# design.net
KiCad netlist of a schematic drawn in Altium Designer
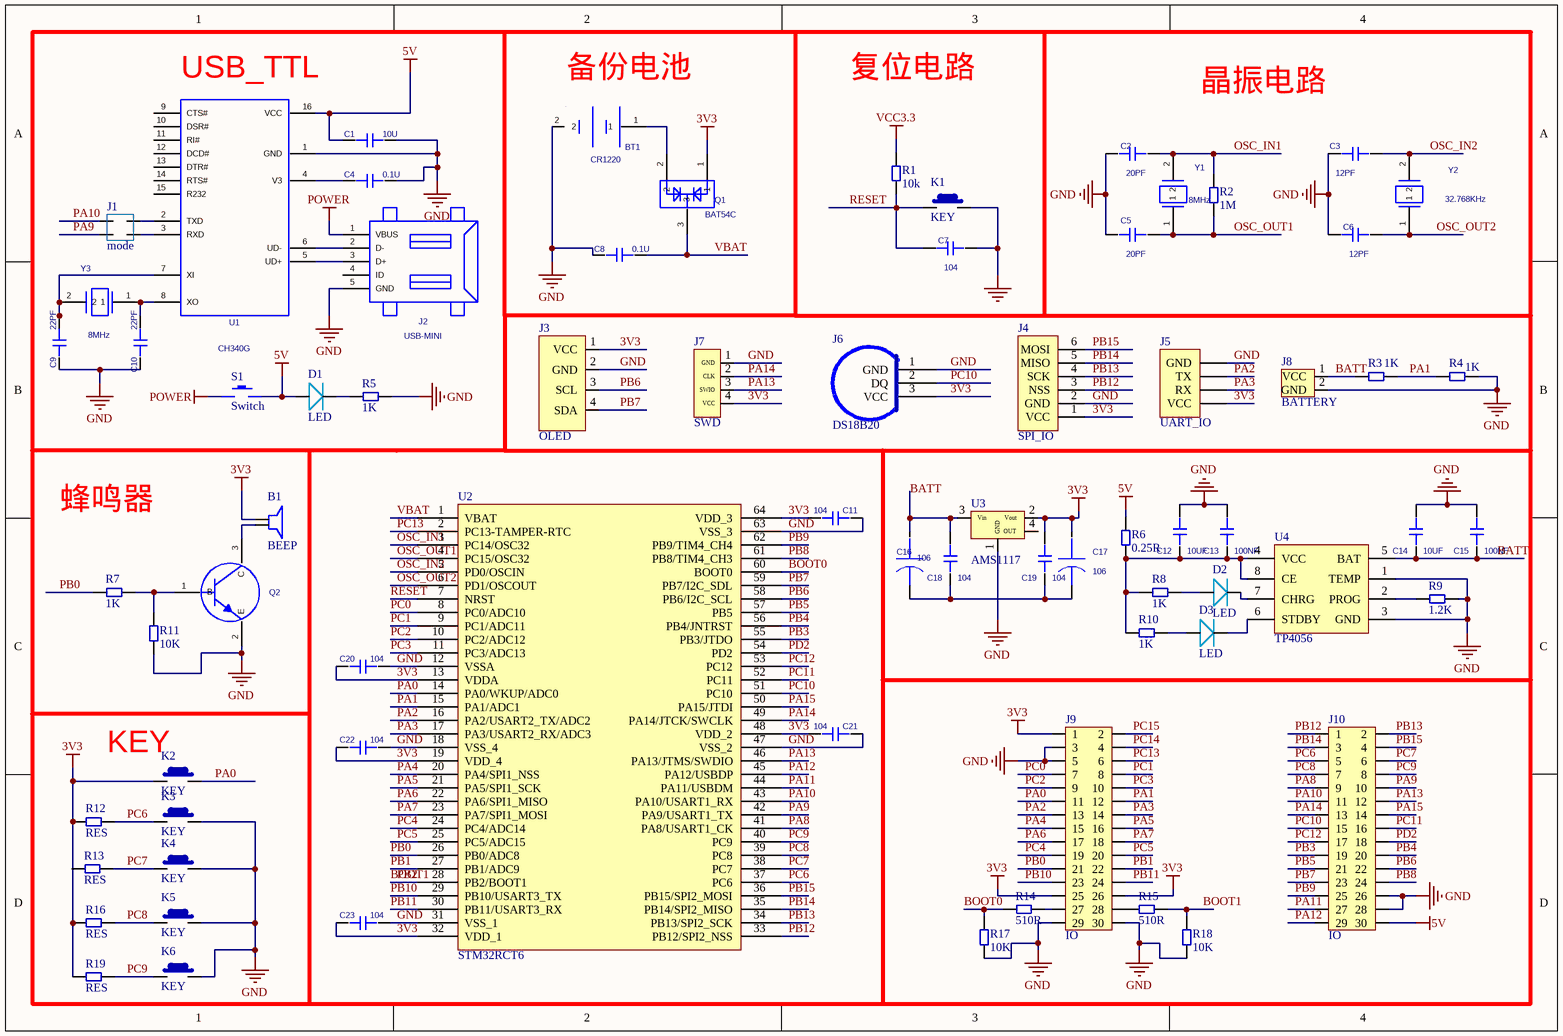
[diagram p0: 创意时钟.SchDoc]

(export (version "E")
  (design (tool "Eeschema 10.0.6"))
  (components
    (comp (ref "B1") (value "BEEP") (footprint "BEEP-9.5X5.5") (libsource (lib "AG") (part "BEEP")))
    (comp (ref "BT1") (value "CR1220") (footprint "BATERY") (libsource (lib "MINI-V3") (part "CR1220")))
    (comp (ref "C1")
      (value "10U")
      (footprint "RES_0603_FIRE")
      (description "0603")
      (fields (field (name "TOLERANCE") "+-5%") (field (name "Comment") "CAP_10P_0603_FIRE"))
      (libsource (lib "MINI-V3") (part "CAP_10P_0603_FIRE"))
    )
    (comp (ref "C2")
      (value "20PF")
      (footprint "CAP_0603_FIRE")
      (fields (field (name "Comment") "CAP_20P_0603_FIRE"))
      (libsource (lib "MINI-V3") (part "CAP_20P_0603_FIRE"))
    )
    (comp (ref "C3")
      (value "12PF")
      (footprint "CAP_0603_FIRE")
      (fields (field (name "Comment") "CAP_20P_0603_FIRE"))
      (libsource (lib "MINI-V3") (part "CAP_20P_0603_FIRE"))
    )
    (comp (ref "C4")
      (value "0.1U")
      (footprint "RES_0603_FIRE")
      (description "0603")
      (fields (field (name "TOLERANCE") "+-5%") (field (name "Comment") "CAP_10P_0603_FIRE"))
      (libsource (lib "MINI-V3") (part "CAP_10P_0603_FIRE"))
    )
    (comp (ref "C5")
      (value "20PF")
      (footprint "CAP_0603_FIRE")
      (fields (field (name "Comment") "CAP_20P_0603_FIRE"))
      (libsource (lib "MINI-V3") (part "CAP_20P_0603_FIRE"))
    )
    (comp (ref "C6")
      (value "12PF")
      (footprint "CAP_0603_FIRE")
      (fields (field (name "Comment") "CAP_20P_0603_FIRE"))
      (libsource (lib "MINI-V3") (part "CAP_20P_0603_FIRE"))
    )
    (comp (ref "C7")
      (value "104")
      (footprint "CAP_0603_FIRE")
      (fields (field (name "Comment") "CAP_20P_0603_FIRE"))
      (libsource (lib "MINI-V3") (part "CAP_20P_0603_FIRE"))
    )
    (comp (ref "C8")
      (value "0.1U")
      (footprint "RES_0603_FIRE")
      (description "0603")
      (fields (field (name "TOLERANCE") "+-5%") (field (name "Comment") "CAP_10P_0603_FIRE"))
      (libsource (lib "MINI-V3") (part "CAP_10P_0603_FIRE"))
    )
    (comp (ref "C9")
      (value "22PF")
      (footprint "CAP_0603_FIRE")
      (fields (field (name "Comment") "CAP_20P_0603_FIRE"))
      (libsource (lib "MINI-V3") (part "CAP_20P_0603_FIRE"))
    )
    (comp (ref "C10")
      (value "22PF")
      (footprint "CAP_0603_FIRE")
      (fields (field (name "Comment") "CAP_20P_0603_FIRE"))
      (libsource (lib "MINI-V3") (part "CAP_20P_0603_FIRE"))
    )
    (comp (ref "C11")
      (value "104")
      (footprint "CAP_0603_FIRE")
      (fields (field (name "Comment") "CAP_20P_0603_FIRE"))
      (libsource (lib "MINI-V3") (part "CAP_20P_0603_FIRE"))
    )
    (comp (ref "C12")
      (value "10UF")
      (footprint "RES_0603_FIRE")
      (description "0603")
      (fields (field (name "TOLERANCE") "+-5%") (field (name "Comment") "CAP_10P_0603_FIRE"))
      (libsource (lib "MINI-V3") (part "CAP_10P_0603_FIRE"))
    )
    (comp (ref "C13")
      (value "100NF")
      (footprint "RES_0603_FIRE")
      (description "0603")
      (fields (field (name "TOLERANCE") "+-5%") (field (name "Comment") "CAP_10P_0603_FIRE"))
      (libsource (lib "MINI-V3") (part "CAP_10P_0603_FIRE"))
    )
    (comp (ref "C14")
      (value "10UF")
      (footprint "RES_0603_FIRE")
      (description "0603")
      (fields (field (name "TOLERANCE") "+-5%") (field (name "Comment") "CAP_10P_0603_FIRE"))
      (libsource (lib "MINI-V3") (part "CAP_10P_0603_FIRE"))
    )
    (comp (ref "C15")
      (value "100NF")
      (footprint "RES_0603_FIRE")
      (description "0603")
      (fields (field (name "TOLERANCE") "+-5%") (field (name "Comment") "CAP_10P_0603_FIRE"))
      (libsource (lib "MINI-V3") (part "CAP_10P_0603_FIRE"))
    )
    (comp (ref "C16")
      (value "106")
      (footprint "CAP+_47UF_FIRE")
      (fields (field (name "Comment") "CAP+_47UF_FIRE"))
      (libsource (lib "MINI-V3") (part "CAP+_47UF_FIRE"))
    )
    (comp (ref "C17")
      (value "106")
      (footprint "CAP+_47UF_FIRE")
      (fields (field (name "Comment") "CAP+_47UF_FIRE"))
      (libsource (lib "MINI-V3") (part "CAP+_47UF_FIRE"))
    )
    (comp (ref "C18")
      (value "104")
      (footprint "RES_0603_FIRE")
      (description "0603")
      (fields (field (name "TOLERANCE") "+-5%") (field (name "Comment") "CAP_10P_0603_FIRE"))
      (libsource (lib "MINI-V3") (part "CAP_10P_0603_FIRE"))
    )
    (comp (ref "C19")
      (value "104")
      (footprint "RES_0603_FIRE")
      (description "0603")
      (fields (field (name "TOLERANCE") "+-5%") (field (name "Comment") "CAP_10P_0603_FIRE"))
      (libsource (lib "MINI-V3") (part "CAP_10P_0603_FIRE"))
    )
    (comp (ref "C20")
      (value "104")
      (footprint "CAP_0603_FIRE")
      (fields (field (name "Comment") "CAP_20P_0603_FIRE"))
      (libsource (lib "MINI-V3") (part "CAP_20P_0603_FIRE"))
    )
    (comp (ref "C21")
      (value "104")
      (footprint "CAP_0603_FIRE")
      (fields (field (name "Comment") "CAP_20P_0603_FIRE"))
      (libsource (lib "MINI-V3") (part "CAP_20P_0603_FIRE"))
    )
    (comp (ref "C22")
      (value "104")
      (footprint "CAP_0603_FIRE")
      (fields (field (name "Comment") "CAP_20P_0603_FIRE"))
      (libsource (lib "MINI-V3") (part "CAP_20P_0603_FIRE"))
    )
    (comp (ref "C23")
      (value "104")
      (footprint "CAP_0603_FIRE")
      (fields (field (name "Comment") "CAP_20P_0603_FIRE"))
      (libsource (lib "MINI-V3") (part "CAP_20P_0603_FIRE"))
    )
    (comp (ref "D1") (value "LED") (footprint "0603_R_JX") (libsource (lib "Schlib1") (part "LED")))
    (comp (ref "D2") (value "LED") (footprint "0603_R_JX") (libsource (lib "Schlib1") (part "LED")))
    (comp (ref "D3") (value "LED") (footprint "0603_R_JX") (libsource (lib "Schlib1") (part "LED")))
    (comp (ref "J1") (value "mode") (footprint "mode") (libsource (lib "Schlib1") (part "mode")))
    (comp (ref "J2")
      (value "USB-MINI")
      (footprint "USB_MINI_B_FE_JX")
      (libsource (lib "MINI-V3") (part "USB-MINI"))
    )
    (comp (ref "J3") (value "OLED") (footprint "OLED") (libsource (lib "aaa") (part "OLED")))
    (comp (ref "J4") (value "SPI_IO") (footprint "SPI_IO") (libsource (lib "Schlib1") (part "SPI_IO")))
    (comp (ref "J5") (value "UART_IO") (footprint "USART_IO") (libsource (lib "Schlib1") (part "UART_IO")))
    (comp (ref "J6") (value "DS18B20") (footprint "DS18B20") (libsource (lib "Schlib1") (part "DS18B20")))
    (comp (ref "J7") (value "SWD") (footprint "SWD") (libsource (lib "aaa") (part "SWD")))
    (comp (ref "J8")
      (value "BATTERY")
      (footprint "XH_2501R_2P_LOCKED_JX")
      (libsource (lib "Schlib1") (part "BATTER"))
    )
    (comp (ref "J9") (value "IO") (footprint "IO") (libsource (lib "Schlib1") (part "IO")))
    (comp (ref "J10") (value "IO") (footprint "IO") (libsource (lib "Schlib1") (part "IO")))
    (comp (ref "K1") (value "KEY") (footprint "KEY") (libsource (lib "Schlib1") (part "KEY")))
    (comp (ref "K2") (value "KEY") (footprint "KEY") (libsource (lib "Schlib1") (part "KEY")))
    (comp (ref "K3") (value "KEY") (footprint "KEY") (libsource (lib "Schlib1") (part "KEY")))
    (comp (ref "K4") (value "KEY") (footprint "KEY") (libsource (lib "Schlib1") (part "KEY")))
    (comp (ref "K5") (value "KEY") (footprint "KEY") (libsource (lib "Schlib1") (part "KEY")))
    (comp (ref "K6") (value "KEY") (footprint "KEY") (libsource (lib "Schlib1") (part "KEY")))
    (comp (ref "Q1") (value "BAT54C") (footprint "SOT-23") (libsource (lib "MINI-V3") (part "BAT54C")))
    (comp (ref "Q2")
      (value "8050")
      (footprint "SOT-23")
      (description "NPN")
      (libsource (lib "MINI-V3") (part "8050"))
    )
    (comp (ref "R1") (value "10k") (footprint "0805") (libsource (lib "Schlib1") (part "RES")))
    (comp (ref "R2") (value "1M") (footprint "0805") (libsource (lib "Schlib1") (part "RES")))
    (comp (ref "R3") (value "1K") (footprint "0805") (libsource (lib "Schlib1") (part "RES")))
    (comp (ref "R4") (value "1K") (footprint "0805") (libsource (lib "Schlib1") (part "RES")))
    (comp (ref "R5") (value "1K") (footprint "0805") (libsource (lib "Schlib1") (part "RES")))
    (comp (ref "R6") (value "0.25R") (footprint "0805") (libsource (lib "Schlib1") (part "RES")))
    (comp (ref "R7") (value "1K") (footprint "0805") (libsource (lib "Schlib1") (part "RES")))
    (comp (ref "R8") (value "1K") (footprint "0805") (libsource (lib "Schlib1") (part "RES")))
    (comp (ref "R9") (value "1.2K") (footprint "0805") (libsource (lib "Schlib1") (part "RES")))
    (comp (ref "R10") (value "1K") (footprint "0805") (libsource (lib "Schlib1") (part "RES")))
    (comp (ref "R11") (value "10K") (footprint "0805") (libsource (lib "Schlib1") (part "RES")))
    (comp (ref "R12") (value "RES") (footprint "0805") (libsource (lib "Schlib1") (part "RES")))
    (comp (ref "R13") (value "RES") (footprint "0805") (libsource (lib "Schlib1") (part "RES")))
    (comp (ref "R14") (value "510R") (footprint "0805") (libsource (lib "Schlib1") (part "RES")))
    (comp (ref "R15") (value "510R") (footprint "0805") (libsource (lib "Schlib1") (part "RES")))
    (comp (ref "R16") (value "RES") (footprint "0805") (libsource (lib "Schlib1") (part "RES")))
    (comp (ref "R17") (value "10K") (footprint "0805") (libsource (lib "Schlib1") (part "RES")))
    (comp (ref "R18") (value "10K") (footprint "0805") (libsource (lib "Schlib1") (part "RES")))
    (comp (ref "R19") (value "RES") (footprint "0805") (libsource (lib "Schlib1") (part "RES")))
    (comp (ref "S1") (value "Switch") (footprint "SWITCH") (libsource (lib "aaa") (part "Switch")))
    (comp (ref "U1") (value "CH340G") (footprint "SOP16") (libsource (lib "MINI-V3") (part "CH340G")))
    (comp (ref "U2") (value "STM32RCT6") (footprint "LQFP64") (libsource (lib "Schlib1") (part "STM32RCT6")))
    (comp (ref "U3") (value "AMS1117") (footprint "AMS-1117-3.3") (libsource (lib "aaa") (part "AMS1117")))
    (comp (ref "U4")
      (value "TP4056")
      (footprint "SOP8_150MIL_JX")
      (libsource (lib "Schlib1") (part "TP4056"))
    )
    (comp (ref "Y1")
      (value "8MHz")
      (footprint "XTAL_socket")
      (description "CRYSTAL")
      (fields (field (name "Comment") "XTAL_8M_FIRE"))
      (libsource (lib "MINI-V3") (part "XTAL_8M_FIRE"))
    )
    (comp (ref "Y2")
      (value "32.768KHz")
      (footprint "CRYS-3X8")
      (description "CRYSTAL")
      (fields (field (name "Comment") "XTAL_32.768KHZ_FIRE"))
      (libsource (lib "MINI-V3") (part "XTAL_32.768KHZ_FIRE"))
    )
    (comp (ref "Y3")
      (value "8MHz")
      (footprint "XTAL_socket")
      (description "CRYSTAL")
      (fields (field (name "Comment") "XTAL_8M_FIRE"))
      (libsource (lib "MINI-V3") (part "XTAL_8M_FIRE"))
    )
  )
  (nets
    (net (code "1") (name "/BATT") (class "Default")
      (node (ref "C14") (pin "1") (pinfunction "1_1") (pintype "passive"))
      (node (ref "C15") (pin "1") (pinfunction "1_1") (pintype "passive"))
      (node (ref "C16") (pin "1") (pinfunction "1_1") (pintype "passive"))
      (node (ref "C18") (pin "2") (pinfunction "2_2") (pintype "passive"))
      (node (ref "J8") (pin "1") (pinfunction "VCC_1") (pintype "passive"))
      (node (ref "R3") (pin "1") (pintype "passive"))
      (node (ref "U3") (pin "3") (pinfunction "Vin_3") (pintype "passive"))
      (node (ref "U4") (pin "5") (pinfunction "BAT_5") (pintype "passive"))
    )
    (net (code "2") (name "/BOOT0") (class "Default")
      (node (ref "R14") (pin "1") (pintype "passive"))
      (node (ref "R17") (pin "2") (pintype "passive"))
      (node (ref "U2") (pin "60") (pinfunction "BOOT0_60") (pintype "passive"))
    )
    (net (code "3") (name "/BOOT1") (class "Default")
      (node (ref "R15") (pin "2") (pintype "passive"))
      (node (ref "R18") (pin "2") (pintype "passive"))
      (node (ref "U2") (pin "28") (pinfunction "PB2/BOOT1_28") (pintype "passive"))
    )
    (net (code "4") (name "/OSC_IN1") (class "Default")
      (node (ref "C2") (pin "2") (pinfunction "2_2") (pintype "passive"))
      (node (ref "R2") (pin "2") (pintype "passive"))
      (node (ref "U2") (pin "3") (pinfunction "PC14/OSC32_3") (pintype "passive"))
      (node (ref "Y1") (pin "2") (pinfunction "2_2") (pintype "passive"))
    )
    (net (code "5") (name "/OSC_IN2") (class "Default")
      (node (ref "C3") (pin "2") (pinfunction "2_2") (pintype "passive"))
      (node (ref "U2") (pin "5") (pinfunction "PD0/OSCIN_5") (pintype "passive"))
      (node (ref "Y2") (pin "2") (pinfunction "2_2") (pintype "passive"))
    )
    (net (code "6") (name "/OSC_OUT1") (class "Default")
      (node (ref "C5") (pin "2") (pinfunction "2_2") (pintype "passive"))
      (node (ref "R2") (pin "1") (pintype "passive"))
      (node (ref "U2") (pin "4") (pinfunction "PC15/OSC32_4") (pintype "passive"))
      (node (ref "Y1") (pin "1") (pinfunction "1_1") (pintype "passive"))
    )
    (net (code "7") (name "/OSC_OUT2") (class "Default")
      (node (ref "C6") (pin "2") (pinfunction "2_2") (pintype "passive"))
      (node (ref "U2") (pin "6") (pinfunction "PD1/OSCOUT_6") (pintype "passive"))
      (node (ref "Y2") (pin "1") (pinfunction "1_1") (pintype "passive"))
    )
    (net (code "8") (name "/PA0") (class "Default")
      (node (ref "J9") (pin "11") (pinfunction "11_11") (pintype "passive"))
      (node (ref "K2") (pin "2") (pintype "passive"))
      (node (ref "U2") (pin "14") (pinfunction "PA0/WKUP/ADC0_14") (pintype "passive"))
    )
    (net (code "9") (name "/PA1") (class "Default")
      (node (ref "J9") (pin "12") (pinfunction "12_12") (pintype "passive"))
      (node (ref "R3") (pin "2") (pintype "passive"))
      (node (ref "R4") (pin "1") (pintype "passive"))
      (node (ref "U2") (pin "15") (pinfunction "PA1/ADC1_15") (pintype "passive"))
    )
    (net (code "10") (name "/PA2") (class "Default")
      (node (ref "J5") (pin "3") (pinfunction "TX_3") (pintype "passive"))
      (node (ref "J9") (pin "13") (pinfunction "13_13") (pintype "passive"))
      (node (ref "U2") (pin "16") (pinfunction "PA2/USART2_TX/ADC2_16") (pintype "passive"))
    )
    (net (code "11") (name "/PA3") (class "Default")
      (node (ref "J5") (pin "2") (pinfunction "RX_2") (pintype "passive"))
      (node (ref "J9") (pin "14") (pinfunction "14_14") (pintype "passive"))
      (node (ref "U2") (pin "17") (pinfunction "PA3/USART2_RX/ADC3_17") (pintype "passive"))
    )
    (net (code "12") (name "/PA4") (class "Default")
      (node (ref "J9") (pin "15") (pinfunction "15_15") (pintype "passive"))
      (node (ref "U2") (pin "20") (pinfunction "PA4/SPI1_NSS_20") (pintype "passive"))
    )
    (net (code "13") (name "/PA5") (class "Default")
      (node (ref "J9") (pin "16") (pinfunction "16_16") (pintype "passive"))
      (node (ref "U2") (pin "21") (pinfunction "PA5/SPI1_SCK_21") (pintype "passive"))
    )
    (net (code "14") (name "/PA6") (class "Default")
      (node (ref "J9") (pin "17") (pinfunction "17_17") (pintype "passive"))
      (node (ref "U2") (pin "22") (pinfunction "PA6/SPI1_MISO_22") (pintype "passive"))
    )
    (net (code "15") (name "/PA7") (class "Default")
      (node (ref "J9") (pin "18") (pinfunction "18_18") (pintype "passive"))
      (node (ref "U2") (pin "23") (pinfunction "PA7/SPI1_MOSI_23") (pintype "passive"))
    )
    (net (code "16") (name "/PA8") (class "Default")
      (node (ref "J10") (pin "9") (pinfunction "9_9") (pintype "passive"))
      (node (ref "U2") (pin "41") (pinfunction "PA8/USART1_CK_41") (pintype "passive"))
    )
    (net (code "17") (name "/PA9") (class "Default")
      (node (ref "J1") (pin "2") (pintype "passive"))
      (node (ref "J10") (pin "10") (pinfunction "10_10") (pintype "passive"))
      (node (ref "U2") (pin "42") (pinfunction "PA9/USART1_TX_42") (pintype "passive"))
    )
    (net (code "18") (name "/PA10") (class "Default")
      (node (ref "J1") (pin "1") (pintype "passive"))
      (node (ref "J10") (pin "11") (pinfunction "11_11") (pintype "passive"))
      (node (ref "U2") (pin "43") (pinfunction "PA10/USART1_RX_43") (pintype "passive"))
    )
    (net (code "19") (name "/PA11") (class "Default")
      (node (ref "J10") (pin "27") (pinfunction "27_27") (pintype "passive"))
      (node (ref "U2") (pin "44") (pinfunction "PA11/USBDM_44") (pintype "passive"))
    )
    (net (code "20") (name "/PA12") (class "Default")
      (node (ref "J10") (pin "29") (pinfunction "29_29") (pintype "passive"))
      (node (ref "U2") (pin "45") (pinfunction "PA12/USBDP_45") (pintype "passive"))
    )
    (net (code "21") (name "/PA13") (class "Default")
      (node (ref "J10") (pin "12") (pinfunction "12_12") (pintype "passive"))
      (node (ref "J7") (pin "3") (pinfunction "SWIO_3") (pintype "passive"))
      (node (ref "U2") (pin "46") (pinfunction "PA13/JTMS/SWDIO_46") (pintype "passive"))
    )
    (net (code "22") (name "/PA14") (class "Default")
      (node (ref "J10") (pin "13") (pinfunction "13_13") (pintype "passive"))
      (node (ref "J7") (pin "2") (pinfunction "CLK_2") (pintype "passive"))
      (node (ref "U2") (pin "49") (pinfunction "PA14/JTCK/SWCLK_49") (pintype "passive"))
    )
    (net (code "23") (name "/PA15") (class "Default")
      (node (ref "J10") (pin "14") (pinfunction "14_14") (pintype "passive"))
      (node (ref "U2") (pin "50") (pinfunction "PA15/JTDI_50") (pintype "passive"))
    )
    (net (code "24") (name "/PB0") (class "Default")
      (node (ref "J9") (pin "21") (pinfunction "21_21") (pintype "passive"))
      (node (ref "R7") (pin "1") (pintype "passive"))
      (node (ref "U2") (pin "26") (pinfunction "PB0/ADC8_26") (pintype "passive"))
    )
    (net (code "25") (name "/PB1") (class "Default")
      (node (ref "J9") (pin "22") (pinfunction "22_22") (pintype "passive"))
      (node (ref "U2") (pin "27") (pinfunction "PB1/ADC9_27") (pintype "passive"))
    )
    (net (code "26") (name "/PB3") (class "Default")
      (node (ref "J10") (pin "19") (pinfunction "19_19") (pintype "passive"))
      (node (ref "U2") (pin "55") (pinfunction "PB3/JTDO_55") (pintype "passive"))
    )
    (net (code "27") (name "/PB4") (class "Default")
      (node (ref "J10") (pin "20") (pinfunction "20_20") (pintype "passive"))
      (node (ref "U2") (pin "56") (pinfunction "PB4/JNTRST_56") (pintype "passive"))
    )
    (net (code "28") (name "/PB5") (class "Default")
      (node (ref "J10") (pin "21") (pinfunction "21_21") (pintype "passive"))
      (node (ref "U2") (pin "57") (pinfunction "PB5_57") (pintype "passive"))
    )
    (net (code "29") (name "/PB6") (class "Default")
      (node (ref "J10") (pin "22") (pinfunction "22_22") (pintype "passive"))
      (node (ref "J3") (pin "3") (pinfunction "SCL_3") (pintype "passive"))
      (node (ref "U2") (pin "58") (pinfunction "PB6/I2C_SCL_58") (pintype "passive"))
    )
    (net (code "30") (name "/PB7") (class "Default")
      (node (ref "J10") (pin "23") (pinfunction "23_23") (pintype "passive"))
      (node (ref "J3") (pin "4") (pinfunction "SDA_4") (pintype "passive"))
      (node (ref "U2") (pin "59") (pinfunction "PB7/I2C_SDL_59") (pintype "passive"))
    )
    (net (code "31") (name "/PB8") (class "Default")
      (node (ref "J10") (pin "24") (pinfunction "24_24") (pintype "passive"))
      (node (ref "U2") (pin "61") (pinfunction "PB8/TIM4_CH3_61") (pintype "passive"))
    )
    (net (code "32") (name "/PB9") (class "Default")
      (node (ref "J10") (pin "25") (pinfunction "25_25") (pintype "passive"))
      (node (ref "U2") (pin "62") (pinfunction "PB9/TIM4_CH4_62") (pintype "passive"))
    )
    (net (code "33") (name "/PB10") (class "Default")
      (node (ref "J9") (pin "23") (pinfunction "23_23") (pintype "passive"))
      (node (ref "U2") (pin "29") (pinfunction "PB10/USART3_TX_29") (pintype "passive"))
    )
    (net (code "34") (name "/PB11") (class "Default")
      (node (ref "J9") (pin "24") (pinfunction "24_24") (pintype "passive"))
      (node (ref "U2") (pin "30") (pinfunction "PB11/USART3_RX_30") (pintype "passive"))
    )
    (net (code "35") (name "/PB12") (class "Default")
      (node (ref "J10") (pin "1") (pinfunction "1_1") (pintype "passive"))
      (node (ref "J4") (pin "3") (pinfunction "NSS_3") (pintype "passive"))
      (node (ref "U2") (pin "33") (pinfunction "PB12/SPI2_NSS_33") (pintype "passive"))
    )
    (net (code "36") (name "/PB13") (class "Default")
      (node (ref "J10") (pin "2") (pinfunction "2_2") (pintype "passive"))
      (node (ref "J4") (pin "4") (pinfunction "SCK_4") (pintype "passive"))
      (node (ref "U2") (pin "34") (pinfunction "PB13/SPI2_SCK_34") (pintype "passive"))
    )
    (net (code "37") (name "/PB14") (class "Default")
      (node (ref "J10") (pin "3") (pinfunction "3_3") (pintype "passive"))
      (node (ref "J4") (pin "5") (pinfunction "MISO_5") (pintype "passive"))
      (node (ref "U2") (pin "35") (pinfunction "PB14/SPI2_MISO_35") (pintype "passive"))
    )
    (net (code "38") (name "/PB15") (class "Default")
      (node (ref "J10") (pin "4") (pinfunction "4_4") (pintype "passive"))
      (node (ref "J4") (pin "6") (pinfunction "MOSI_6") (pintype "passive"))
      (node (ref "U2") (pin "36") (pinfunction "PB15/SPI2_MOSI_36") (pintype "passive"))
    )
    (net (code "39") (name "/PC0") (class "Default")
      (node (ref "J9") (pin "7") (pinfunction "7_7") (pintype "passive"))
      (node (ref "U2") (pin "8") (pinfunction "PC0/ADC10_8") (pintype "passive"))
    )
    (net (code "40") (name "/PC1") (class "Default")
      (node (ref "J9") (pin "8") (pinfunction "8_8") (pintype "passive"))
      (node (ref "U2") (pin "9") (pinfunction "PC1/ADC11_9") (pintype "passive"))
    )
    (net (code "41") (name "/PC2") (class "Default")
      (node (ref "J9") (pin "9") (pinfunction "9_9") (pintype "passive"))
      (node (ref "U2") (pin "10") (pinfunction "PC2/ADC12_10") (pintype "passive"))
    )
    (net (code "42") (name "/PC3") (class "Default")
      (node (ref "J9") (pin "10") (pinfunction "10_10") (pintype "passive"))
      (node (ref "U2") (pin "11") (pinfunction "PC3/ADC13_11") (pintype "passive"))
    )
    (net (code "43") (name "/PC4") (class "Default")
      (node (ref "J9") (pin "19") (pinfunction "19_19") (pintype "passive"))
      (node (ref "U2") (pin "24") (pinfunction "PC4/ADC14_24") (pintype "passive"))
    )
    (net (code "44") (name "/PC5") (class "Default")
      (node (ref "J9") (pin "20") (pinfunction "20_20") (pintype "passive"))
      (node (ref "U2") (pin "25") (pinfunction "PC5/ADC15_25") (pintype "passive"))
    )
    (net (code "45") (name "/PC6") (class "Default")
      (node (ref "J10") (pin "5") (pinfunction "5_5") (pintype "passive"))
      (node (ref "K3") (pin "1") (pintype "passive"))
      (node (ref "R12") (pin "2") (pintype "passive"))
      (node (ref "U2") (pin "37") (pinfunction "PC6_37") (pintype "passive"))
    )
    (net (code "46") (name "/PC7") (class "Default")
      (node (ref "J10") (pin "6") (pinfunction "6_6") (pintype "passive"))
      (node (ref "K4") (pin "1") (pintype "passive"))
      (node (ref "R13") (pin "2") (pintype "passive"))
      (node (ref "U2") (pin "38") (pinfunction "PC7_38") (pintype "passive"))
    )
    (net (code "47") (name "/PC8") (class "Default")
      (node (ref "J10") (pin "7") (pinfunction "7_7") (pintype "passive"))
      (node (ref "K5") (pin "1") (pintype "passive"))
      (node (ref "R16") (pin "2") (pintype "passive"))
      (node (ref "U2") (pin "39") (pinfunction "PC8_39") (pintype "passive"))
    )
    (net (code "48") (name "/PC9") (class "Default")
      (node (ref "J10") (pin "8") (pinfunction "8_8") (pintype "passive"))
      (node (ref "K6") (pin "1") (pintype "passive"))
      (node (ref "R19") (pin "2") (pintype "passive"))
      (node (ref "U2") (pin "40") (pinfunction "PC9_40") (pintype "passive"))
    )
    (net (code "49") (name "/PC10") (class "Default")
      (node (ref "J10") (pin "15") (pinfunction "15_15") (pintype "passive"))
      (node (ref "J6") (pin "2") (pinfunction "DQ_2") (pintype "passive"))
      (node (ref "U2") (pin "51") (pinfunction "PC10_51") (pintype "passive"))
    )
    (net (code "50") (name "/PC11") (class "Default")
      (node (ref "J10") (pin "16") (pinfunction "16_16") (pintype "passive"))
      (node (ref "U2") (pin "52") (pinfunction "PC11_52") (pintype "passive"))
    )
    (net (code "51") (name "/PC12") (class "Default")
      (node (ref "J10") (pin "17") (pinfunction "17_17") (pintype "passive"))
      (node (ref "U2") (pin "53") (pinfunction "PC12_53") (pintype "passive"))
    )
    (net (code "52") (name "/PC13") (class "Default")
      (node (ref "J9") (pin "6") (pinfunction "6_6") (pintype "passive"))
      (node (ref "U2") (pin "2") (pinfunction "PC13-TAMPER-RTC_2") (pintype "passive"))
    )
    (net (code "53") (name "/PC14") (class "Default")
      (node (ref "J9") (pin "4") (pinfunction "4_4") (pintype "passive"))
    )
    (net (code "54") (name "/PC15") (class "Default")
      (node (ref "J9") (pin "2") (pinfunction "2_2") (pintype "passive"))
    )
    (net (code "55") (name "/PD2") (class "Default")
      (node (ref "J10") (pin "18") (pinfunction "18_18") (pintype "passive"))
      (node (ref "U2") (pin "54") (pinfunction "PD2_54") (pintype "passive"))
    )
    (net (code "56") (name "/RESET") (class "Default")
      (node (ref "C7") (pin "1") (pinfunction "1_1") (pintype "passive"))
      (node (ref "K1") (pin "1") (pintype "passive"))
      (node (ref "R1") (pin "1") (pintype "passive"))
      (node (ref "U2") (pin "7") (pinfunction "NRST_7") (pintype "passive"))
    )
    (net (code "57") (name "/VBAT") (class "Default")
      (node (ref "C8") (pin "2") (pinfunction "2_2") (pintype "passive"))
      (node (ref "Q1") (pin "3") (pinfunction "3_3") (pintype "passive"))
      (node (ref "U2") (pin "1") (pinfunction "VBAT_1") (pintype "passive"))
    )
    (net (code "58") (name "3V3") (class "Default")
      (node (ref "B1") (pin "1") (pinfunction "1_1") (pintype "passive"))
      (node (ref "C11") (pin "1") (pinfunction "1_1") (pintype "passive"))
      (node (ref "C17") (pin "1") (pinfunction "1_1") (pintype "passive"))
      (node (ref "C19") (pin "2") (pinfunction "2_2") (pintype "passive"))
      (node (ref "C20") (pin "2") (pinfunction "2_2") (pintype "passive"))
      (node (ref "C21") (pin "1") (pinfunction "1_1") (pintype "passive"))
      (node (ref "C22") (pin "2") (pinfunction "2_2") (pintype "passive"))
      (node (ref "C23") (pin "2") (pinfunction "2_2") (pintype "passive"))
      (node (ref "J3") (pin "1") (pinfunction "VCC_1") (pintype "passive"))
      (node (ref "J4") (pin "1") (pinfunction "VCC_1") (pintype "passive"))
      (node (ref "J5") (pin "1") (pinfunction "VCC_1") (pintype "passive"))
      (node (ref "J6") (pin "3") (pinfunction "VCC_3") (pintype "passive"))
      (node (ref "J7") (pin "4") (pinfunction "VCC_4") (pintype "passive"))
      (node (ref "J9") (pin "1") (pinfunction "1_1") (pintype "passive"))
      (node (ref "J9") (pin "25") (pinfunction "25_25") (pintype "passive"))
      (node (ref "J9") (pin "26") (pinfunction "26_26") (pintype "passive"))
      (node (ref "K2") (pin "1") (pintype "passive"))
      (node (ref "Q1") (pin "1") (pinfunction "1_1") (pintype "passive"))
      (node (ref "R12") (pin "1") (pintype "passive"))
      (node (ref "R16") (pin "1") (pintype "passive"))
      (node (ref "R19") (pin "1") (pintype "passive"))
      (node (ref "U2") (pin "13") (pinfunction "VDDA_13") (pintype "passive"))
      (node (ref "U2") (pin "19") (pinfunction "VDD_4_19") (pintype "passive"))
      (node (ref "U2") (pin "32") (pinfunction "VDD_1_32") (pintype "passive"))
      (node (ref "U2") (pin "48") (pinfunction "VDD_2_48") (pintype "passive"))
      (node (ref "U2") (pin "64") (pinfunction "VDD_3_64") (pintype "passive"))
      (node (ref "U3") (pin "2") (pinfunction "Vout_2") (pintype "passive"))
    )
    (net (code "59") (name "5V") (class "Default")
      (node (ref "C1") (pin "1") (pinfunction "1_1") (pintype "passive"))
      (node (ref "D1") (pin "1") (pintype "passive"))
      (node (ref "J10") (pin "30") (pinfunction "30_30") (pintype "passive"))
      (node (ref "R6") (pin "2") (pintype "passive"))
      (node (ref "S1") (pin "2") (pinfunction "VCC_2") (pintype "passive"))
      (node (ref "U1") (pin "16") (pinfunction "VCC_16") (pintype "passive"))
    )
    (net (code "60") (name "GND") (class "Default")
      (node (ref "BT1") (pin "2") (pinfunction "2_2") (pintype "passive"))
      (node (ref "C1") (pin "2") (pinfunction "2_2") (pintype "passive"))
      (node (ref "C10") (pin "1") (pinfunction "1_1") (pintype "passive"))
      (node (ref "C11") (pin "2") (pinfunction "2_2") (pintype "passive"))
      (node (ref "C12") (pin "2") (pinfunction "2_2") (pintype "passive"))
      (node (ref "C13") (pin "2") (pinfunction "2_2") (pintype "passive"))
      (node (ref "C14") (pin "2") (pinfunction "2_2") (pintype "passive"))
      (node (ref "C15") (pin "2") (pinfunction "2_2") (pintype "passive"))
      (node (ref "C2") (pin "1") (pinfunction "1_1") (pintype "passive"))
      (node (ref "C20") (pin "1") (pinfunction "1_1") (pintype "passive"))
      (node (ref "C21") (pin "2") (pinfunction "2_2") (pintype "passive"))
      (node (ref "C22") (pin "1") (pinfunction "1_1") (pintype "passive"))
      (node (ref "C23") (pin "1") (pinfunction "1_1") (pintype "passive"))
      (node (ref "C3") (pin "1") (pinfunction "1_1") (pintype "passive"))
      (node (ref "C4") (pin "2") (pinfunction "2_2") (pintype "passive"))
      (node (ref "C5") (pin "1") (pinfunction "1_1") (pintype "passive"))
      (node (ref "C6") (pin "1") (pinfunction "1_1") (pintype "passive"))
      (node (ref "C7") (pin "2") (pinfunction "2_2") (pintype "passive"))
      (node (ref "C8") (pin "1") (pinfunction "1_1") (pintype "passive"))
      (node (ref "C9") (pin "1") (pinfunction "1_1") (pintype "passive"))
      (node (ref "J10") (pin "26") (pinfunction "26_26") (pintype "passive"))
      (node (ref "J10") (pin "28") (pinfunction "28_28") (pintype "passive"))
      (node (ref "J2") (pin "5") (pinfunction "GND_5") (pintype "passive"))
      (node (ref "J3") (pin "2") (pinfunction "GND_2") (pintype "passive"))
      (node (ref "J4") (pin "2") (pinfunction "GND_2") (pintype "passive"))
      (node (ref "J5") (pin "4") (pinfunction "GND_4") (pintype "passive"))
      (node (ref "J6") (pin "1") (pinfunction "GND_1") (pintype "passive"))
      (node (ref "J7") (pin "1") (pinfunction "GND_1") (pintype "passive"))
      (node (ref "J8") (pin "2") (pinfunction "GND_2") (pintype "passive"))
      (node (ref "J9") (pin "29") (pinfunction "29_29") (pintype "passive"))
      (node (ref "J9") (pin "3") (pinfunction "3_3") (pintype "passive"))
      (node (ref "J9") (pin "30") (pinfunction "30_30") (pintype "passive"))
      (node (ref "J9") (pin "5") (pinfunction "5_5") (pintype "passive"))
      (node (ref "K1") (pin "2") (pintype "passive"))
      (node (ref "K3") (pin "2") (pintype "passive"))
      (node (ref "K4") (pin "2") (pintype "passive"))
      (node (ref "K5") (pin "2") (pintype "passive"))
      (node (ref "K6") (pin "2") (pintype "passive"))
      (node (ref "Q2") (pin "2") (pinfunction "E_2") (pintype "passive"))
      (node (ref "R11") (pin "1") (pintype "passive"))
      (node (ref "R17") (pin "1") (pintype "passive"))
      (node (ref "R18") (pin "1") (pintype "passive"))
      (node (ref "R4") (pin "2") (pintype "passive"))
      (node (ref "R5") (pin "2") (pintype "passive"))
      (node (ref "R9") (pin "2") (pintype "passive"))
      (node (ref "U1") (pin "1") (pinfunction "GND_1") (pintype "passive"))
      (node (ref "U2") (pin "12") (pinfunction "VSSA_12") (pintype "passive"))
      (node (ref "U2") (pin "18") (pinfunction "VSS_4_18") (pintype "passive"))
      (node (ref "U2") (pin "31") (pinfunction "VSS_1_31") (pintype "passive"))
      (node (ref "U2") (pin "47") (pinfunction "VSS_2_47") (pintype "passive"))
      (node (ref "U2") (pin "63") (pinfunction "VSS_3_63") (pintype "passive"))
      (node (ref "U3") (pin "1") (pinfunction "GND_1") (pintype "passive"))
      (node (ref "U4") (pin "1") (pinfunction "TEMP_1") (pintype "passive"))
      (node (ref "U4") (pin "3") (pinfunction "GND_3") (pintype "passive"))
    )
    (net (code "61") (name "Net-(BT1-Pad1)") (class "Default")
      (node (ref "BT1") (pin "1") (pinfunction "1_1") (pintype "passive"))
      (node (ref "Q1") (pin "2") (pinfunction "2_2") (pintype "passive"))
    )
    (net (code "62") (name "Net-(C16-Pad2)") (class "Default")
      (node (ref "C16") (pin "2") (pinfunction "2_2") (pintype "passive"))
      (node (ref "C17") (pin "2") (pinfunction "2_2") (pintype "passive"))
      (node (ref "C18") (pin "1") (pinfunction "1_1") (pintype "passive"))
      (node (ref "C19") (pin "1") (pinfunction "1_1") (pintype "passive"))
    )
    (net (code "63") (name "Net-(D1-Pad2)") (class "Default")
      (node (ref "D1") (pin "2") (pintype "passive"))
      (node (ref "R5") (pin "1") (pintype "passive"))
    )
    (net (code "64") (name "Net-(D2-Pad1)") (class "Default")
      (node (ref "D2") (pin "1") (pintype "passive"))
      (node (ref "R8") (pin "2") (pintype "passive"))
    )
    (net (code "65") (name "Net-(D3-Pad1)") (class "Default")
      (node (ref "D3") (pin "1") (pintype "passive"))
      (node (ref "R10") (pin "2") (pintype "passive"))
    )
    (net (code "66") (name "Net-(J2-D+)") (class "Default")
      (node (ref "J2") (pin "3") (pinfunction "D+_3") (pintype "passive"))
      (node (ref "U1") (pin "5") (pinfunction "UD+_5") (pintype "passive"))
    )
    (net (code "67") (name "Net-(J2-D-)") (class "Default")
      (node (ref "J2") (pin "2") (pinfunction "D-_2") (pintype "passive"))
      (node (ref "U1") (pin "6") (pinfunction "UD-_6") (pintype "passive"))
    )
    (net (code "68") (name "Net-(J9-Pad27)") (class "Default")
      (node (ref "J9") (pin "27") (pinfunction "27_27") (pintype "passive"))
      (node (ref "R14") (pin "2") (pintype "passive"))
    )
    (net (code "69") (name "Net-(J9-Pad28)") (class "Default")
      (node (ref "J9") (pin "28") (pinfunction "28_28") (pintype "passive"))
      (node (ref "R15") (pin "1") (pintype "passive"))
    )
    (net (code "70") (name "Net-(Q2-B)") (class "Default")
      (node (ref "Q2") (pin "1") (pinfunction "B_1") (pintype "passive"))
      (node (ref "R11") (pin "2") (pintype "passive"))
      (node (ref "R7") (pin "2") (pintype "passive"))
    )
    (net (code "71") (name "Net-(Q2-C)") (class "Default")
      (node (ref "B1") (pin "2") (pinfunction "2_2") (pintype "passive"))
      (node (ref "Q2") (pin "3") (pinfunction "C_3") (pintype "passive"))
    )
    (net (code "72") (name "Net-(U1-RXD)") (class "Default")
      (node (ref "J1") (pin "4") (pintype "passive"))
      (node (ref "U1") (pin "3") (pinfunction "RXD_3") (pintype "passive"))
    )
    (net (code "73") (name "Net-(U1-TXD)") (class "Default")
      (node (ref "J1") (pin "3") (pintype "passive"))
      (node (ref "U1") (pin "2") (pinfunction "TXD_2") (pintype "passive"))
    )
    (net (code "74") (name "Net-(U1-V3)") (class "Default")
      (node (ref "C4") (pin "1") (pinfunction "1_1") (pintype "passive"))
      (node (ref "U1") (pin "4") (pinfunction "V3_4") (pintype "passive"))
    )
    (net (code "75") (name "Net-(U1-XI)") (class "Default")
      (node (ref "C9") (pin "2") (pinfunction "2_2") (pintype "passive"))
      (node (ref "U1") (pin "7") (pinfunction "XI_7") (pintype "passive"))
      (node (ref "Y3") (pin "2") (pinfunction "2_2") (pintype "passive"))
    )
    (net (code "76") (name "Net-(U1-XO)") (class "Default")
      (node (ref "C10") (pin "2") (pinfunction "2_2") (pintype "passive"))
      (node (ref "U1") (pin "8") (pinfunction "XO_8") (pintype "passive"))
      (node (ref "Y3") (pin "1") (pinfunction "1_1") (pintype "passive"))
    )
    (net (code "77") (name "Net-(U4-CE)") (class "Default")
      (node (ref "C12") (pin "1") (pinfunction "1_1") (pintype "passive"))
      (node (ref "C13") (pin "1") (pinfunction "1_1") (pintype "passive"))
      (node (ref "R10") (pin "1") (pintype "passive"))
      (node (ref "R6") (pin "1") (pintype "passive"))
      (node (ref "R8") (pin "1") (pintype "passive"))
      (node (ref "U4") (pin "4") (pinfunction "VCC_4") (pintype "passive"))
      (node (ref "U4") (pin "8") (pinfunction "CE_8") (pintype "passive"))
    )
    (net (code "78") (name "Net-(U4-CHRG)") (class "Default")
      (node (ref "D2") (pin "2") (pintype "passive"))
      (node (ref "U4") (pin "7") (pinfunction "CHRG_7") (pintype "passive"))
    )
    (net (code "79") (name "Net-(U4-PROG)") (class "Default")
      (node (ref "R9") (pin "1") (pintype "passive"))
      (node (ref "U4") (pin "2") (pinfunction "PROG_2") (pintype "passive"))
    )
    (net (code "80") (name "Net-(U4-STDBY)") (class "Default")
      (node (ref "D3") (pin "2") (pintype "passive"))
      (node (ref "U4") (pin "6") (pinfunction "STDBY_6") (pintype "passive"))
    )
    (net (code "81") (name "POWER") (class "Default")
      (node (ref "J2") (pin "1") (pinfunction "VBUS_1") (pintype "passive"))
      (node (ref "S1") (pin "1") (pinfunction "VCC_1") (pintype "passive"))
    )
    (net (code "82") (name "VCC3.3") (class "Default") (node (ref "R1") (pin "2") (pintype "passive")))
    (net (code "83") (name "unconnected-(J2-ID-Pad4)") (class "Default")
      (node (ref "J2") (pin "4") (pinfunction "ID_4") (pintype "passive"))
    )
    (net (code "84") (name "unconnected-(R13-Pad1)") (class "Default")
      (node (ref "R13") (pin "1") (pintype "passive"))
    )
    (net (code "85") (name "unconnected-(U1-CTS#-Pad9)") (class "Default")
      (node (ref "U1") (pin "9") (pinfunction "CTS#_9") (pintype "passive"))
    )
    (net (code "86") (name "unconnected-(U1-DCD#-Pad12)") (class "Default")
      (node (ref "U1") (pin "12") (pinfunction "DCD#_12") (pintype "passive"))
    )
    (net (code "87") (name "unconnected-(U1-DSR#-Pad10)") (class "Default")
      (node (ref "U1") (pin "10") (pinfunction "DSR#_10") (pintype "passive"))
    )
    (net (code "88") (name "unconnected-(U1-DTR#-Pad13)") (class "Default")
      (node (ref "U1") (pin "13") (pinfunction "DTR#_13") (pintype "passive"))
    )
    (net (code "89") (name "unconnected-(U1-R232-Pad15)") (class "Default")
      (node (ref "U1") (pin "15") (pinfunction "R232_15") (pintype "passive"))
    )
    (net (code "90") (name "unconnected-(U1-RI#-Pad11)") (class "Default")
      (node (ref "U1") (pin "11") (pinfunction "RI#_11") (pintype "passive"))
    )
    (net (code "91") (name "unconnected-(U1-RTS#-Pad14)") (class "Default")
      (node (ref "U1") (pin "14") (pinfunction "RTS#_14") (pintype "passive"))
    )
    (net (code "92") (name "unconnected-(U3-OUT-Pad4)") (class "Default")
      (node (ref "U3") (pin "4") (pinfunction "OUT_4") (pintype "passive"))
    )
  )
)
